# Sensor.net
KiCad netlist of a schematic drawn in Altium Designer
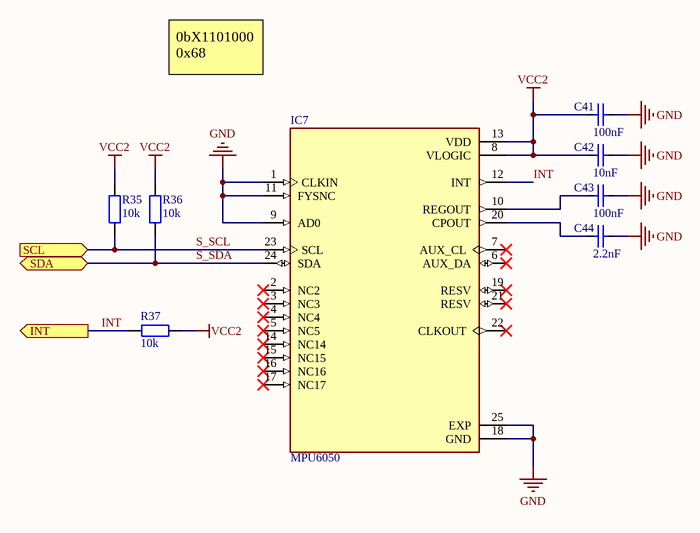
[diagram p0: Sensor.SchDoc]

(export (version "E")
  (design (tool "Eeschema 10.0.6"))
  (components
    (comp (ref "C41")
      (value "100nF")
      (footprint "CAP_0603")
      (description "Capacitor")
      (fields (field (name "PUBLISHER") "Altium Limited"))
      (libsource (lib "My Library") (part "CapSMD"))
    )
    (comp (ref "C42")
      (value "10nF")
      (footprint "CAP_0603")
      (description "Capacitor")
      (fields (field (name "PUBLISHER") "Altium Limited"))
      (libsource (lib "My Library") (part "CapSMD"))
    )
    (comp (ref "C43")
      (value "100nF")
      (footprint "CAP_0603")
      (description "Capacitor")
      (fields (field (name "PUBLISHER") "Altium Limited"))
      (libsource (lib "My Library") (part "CapSMD"))
    )
    (comp (ref "C44")
      (value "2.2nF")
      (footprint "CAP_0603")
      (description "Capacitor")
      (fields (field (name "PUBLISHER") "Altium Limited"))
      (libsource (lib "My Library") (part "CapSMD"))
    )
    (comp (ref "IC7")
      (value "MPU6050")
      (footprint "QFN24")
      (description "3-axis gyroscope, 3-axis accelerometer")
      (libsource (lib "My Library") (part "MPU6050_Chip"))
    )
    (comp (ref "R35")
      (value "10k")
      (footprint "RES-SMD-0603")
      (description "Resistor SMD")
      (fields
        (field (name "MANUFACTURER") "Generic Components")
        (field (name "PUBLISHER") "Altium Hobart Technology Centre")
      )
      (libsource (lib "My Library") (part "Resistor - SMD"))
    )
    (comp (ref "R36")
      (value "10k")
      (footprint "RES-SMD-0603")
      (description "Resistor SMD")
      (fields
        (field (name "MANUFACTURER") "Generic Components")
        (field (name "PUBLISHER") "Altium Hobart Technology Centre")
      )
      (libsource (lib "My Library") (part "Resistor - SMD"))
    )
    (comp (ref "R37")
      (value "10k")
      (footprint "RES-SMD-0603")
      (description "Resistor SMD")
      (fields
        (field (name "MANUFACTURER") "Generic Components")
        (field (name "PUBLISHER") "Altium Hobart Technology Centre")
      )
      (libsource (lib "My Library") (part "Resistor - SMD"))
    )
  )
  (nets
    (net (code "1") (name "/INT") (class "Default")
      (node (ref "IC7") (pin "12") (pinfunction "INT_12") (pintype "output"))
      (node (ref "R37") (pin "2") (pinfunction "2_2") (pintype "passive"))
    )
    (net (code "2") (name "/S_SCL") (class "Default")
      (node (ref "IC7") (pin "23") (pinfunction "SCL_23") (pintype "input"))
      (node (ref "R35") (pin "1") (pinfunction "1_1") (pintype "passive"))
    )
    (net (code "3") (name "/S_SDA") (class "Default")
      (node (ref "IC7") (pin "24") (pinfunction "SDA_24") (pintype "bidirectional"))
      (node (ref "R36") (pin "1") (pinfunction "1_1") (pintype "passive"))
    )
    (net (code "4") (name "GND") (class "Default")
      (node (ref "C41") (pin "1") (pinfunction "1_1") (pintype "passive"))
      (node (ref "C42") (pin "1") (pinfunction "1_1") (pintype "passive"))
      (node (ref "C43") (pin "1") (pinfunction "1_1") (pintype "passive"))
      (node (ref "C44") (pin "1") (pinfunction "1_1") (pintype "passive"))
      (node (ref "IC7") (pin "1") (pinfunction "CLKIN_1") (pintype "input"))
      (node (ref "IC7") (pin "11") (pinfunction "FYSNC_11") (pintype "input"))
      (node (ref "IC7") (pin "18") (pinfunction "GND_18") (pintype "power_in"))
      (node (ref "IC7") (pin "25") (pinfunction "EXP_25") (pintype "power_in"))
      (node (ref "IC7") (pin "9") (pinfunction "AD0_9") (pintype "input"))
    )
    (net (code "5") (name "Net-(IC7-CPOUT)") (class "Default")
      (node (ref "C44") (pin "2") (pinfunction "2_2") (pintype "passive"))
      (node (ref "IC7") (pin "20") (pinfunction "CPOUT_20") (pintype "output"))
    )
    (net (code "6") (name "Net-(IC7-REGOUT)") (class "Default")
      (node (ref "C43") (pin "2") (pinfunction "2_2") (pintype "passive"))
      (node (ref "IC7") (pin "10") (pinfunction "REGOUT_10") (pintype "output"))
    )
    (net (code "7") (name "VCC2") (class "Default")
      (node (ref "C41") (pin "2") (pinfunction "2_2") (pintype "passive"))
      (node (ref "C42") (pin "2") (pinfunction "2_2") (pintype "passive"))
      (node (ref "IC7") (pin "13") (pinfunction "VDD_13") (pintype "power_in"))
      (node (ref "IC7") (pin "8") (pinfunction "VLOGIC_8") (pintype "power_in"))
      (node (ref "R35") (pin "2") (pinfunction "2_2") (pintype "passive"))
      (node (ref "R36") (pin "2") (pinfunction "2_2") (pintype "passive"))
      (node (ref "R37") (pin "1") (pinfunction "1_1") (pintype "passive"))
    )
    (net (code "8") (name "unconnected-(IC7-AUX_CL-Pad7)") (class "Default")
      (node (ref "IC7") (pin "7") (pinfunction "AUX_CL_7") (pintype "output+no_connect"))
    )
    (net (code "9") (name "unconnected-(IC7-AUX_DA-Pad6)") (class "Default")
      (node (ref "IC7") (pin "6") (pinfunction "AUX_DA_6") (pintype "bidirectional+no_connect"))
    )
    (net (code "10") (name "unconnected-(IC7-CLKOUT-Pad22)") (class "Default")
      (node (ref "IC7") (pin "22") (pinfunction "CLKOUT_22") (pintype "output+no_connect"))
    )
    (net (code "11") (name "unconnected-(IC7-NC2-Pad2)") (class "Default")
      (node (ref "IC7") (pin "2") (pinfunction "NC2_2") (pintype "input+no_connect"))
    )
    (net (code "12") (name "unconnected-(IC7-NC3-Pad3)") (class "Default")
      (node (ref "IC7") (pin "3") (pinfunction "NC3_3") (pintype "input+no_connect"))
    )
    (net (code "13") (name "unconnected-(IC7-NC4-Pad4)") (class "Default")
      (node (ref "IC7") (pin "4") (pinfunction "NC4_4") (pintype "input+no_connect"))
    )
    (net (code "14") (name "unconnected-(IC7-NC5-Pad5)") (class "Default")
      (node (ref "IC7") (pin "5") (pinfunction "NC5_5") (pintype "input+no_connect"))
    )
    (net (code "15") (name "unconnected-(IC7-NC14-Pad14)") (class "Default")
      (node (ref "IC7") (pin "14") (pinfunction "NC14_14") (pintype "input+no_connect"))
    )
    (net (code "16") (name "unconnected-(IC7-NC15-Pad15)") (class "Default")
      (node (ref "IC7") (pin "15") (pinfunction "NC15_15") (pintype "input+no_connect"))
    )
    (net (code "17") (name "unconnected-(IC7-NC16-Pad16)") (class "Default")
      (node (ref "IC7") (pin "16") (pinfunction "NC16_16") (pintype "input+no_connect"))
    )
    (net (code "18") (name "unconnected-(IC7-NC17-Pad17)") (class "Default")
      (node (ref "IC7") (pin "17") (pinfunction "NC17_17") (pintype "input+no_connect"))
    )
    (net (code "19") (name "unconnected-(IC7-RESV-Pad19)") (class "Default")
      (node (ref "IC7") (pin "19") (pinfunction "RESV_19") (pintype "bidirectional+no_connect"))
    )
    (net (code "20") (name "unconnected-(IC7-RESV-Pad21)") (class "Default")
      (node (ref "IC7") (pin "21") (pinfunction "RESV_21") (pintype "bidirectional+no_connect"))
    )
  )
)
